# 1-Schematic_SAO_HACKGDL_2025.net
KiCad netlist of a schematic drawn in EasyEDA
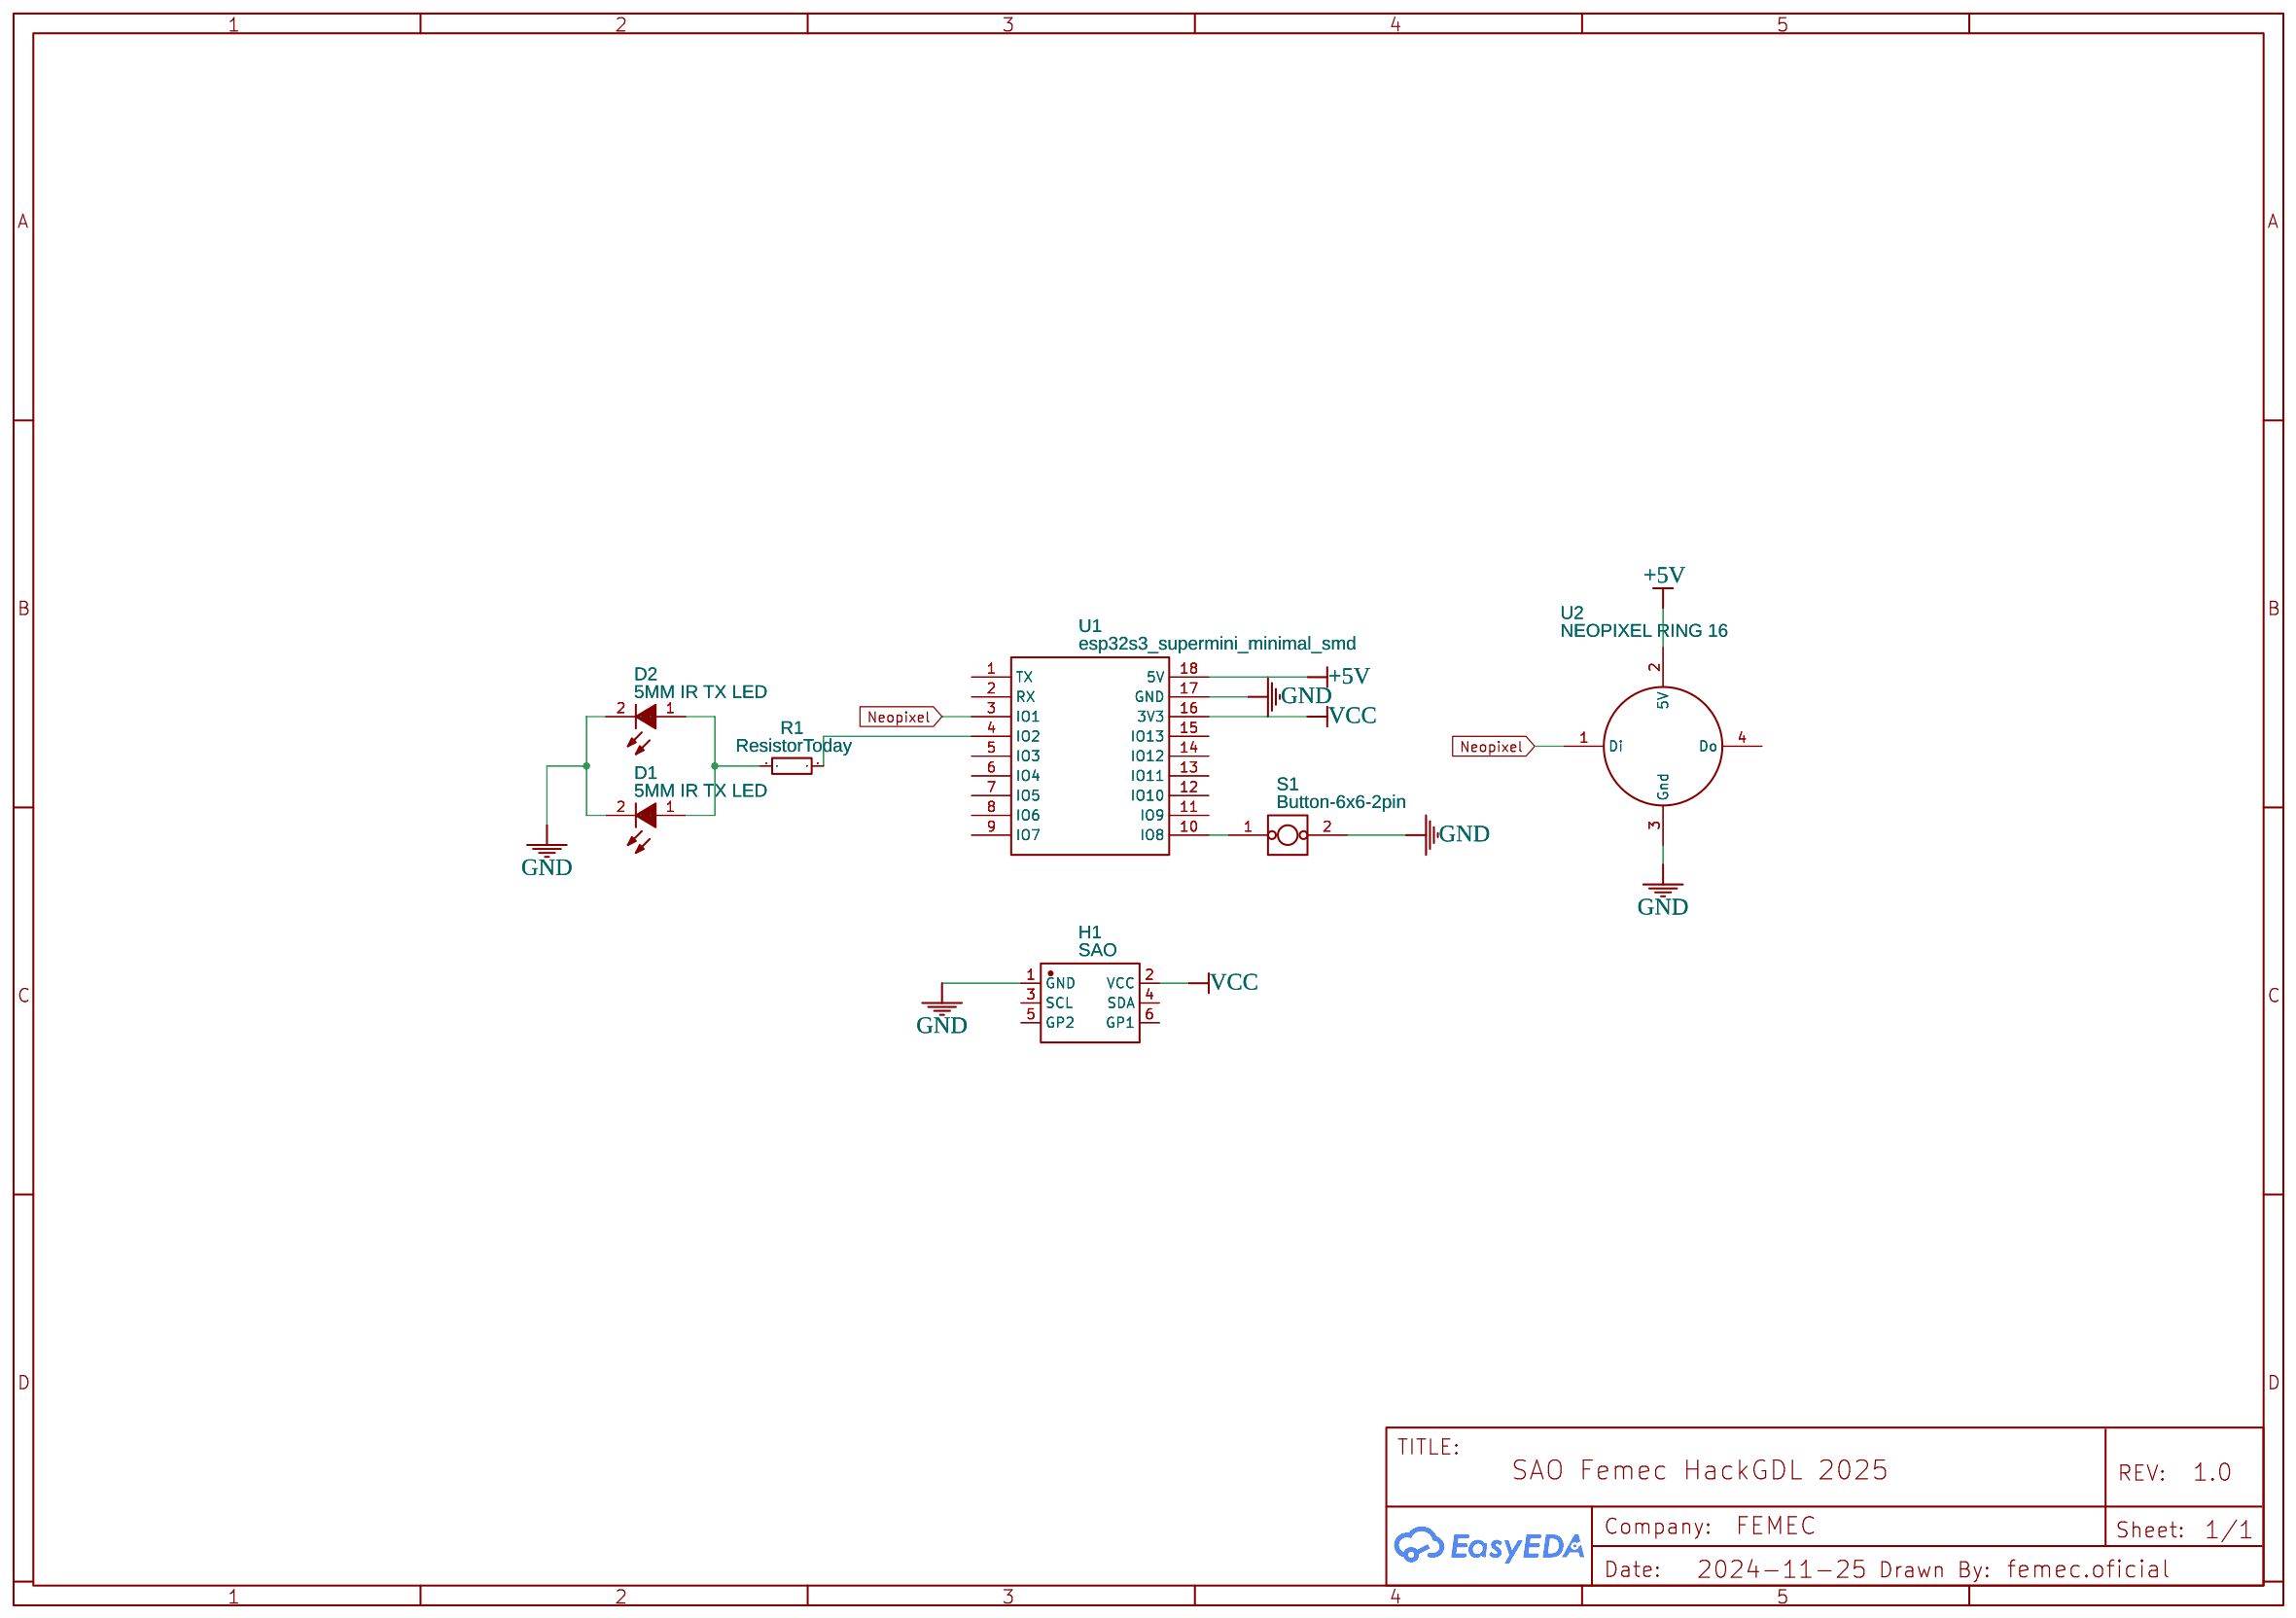
[diagram p0: schematic sheet]

(export (version "E")
  (design (tool "Eeschema 10.0.6"))
  (components
    (comp (ref "D1")
      (value "5MM IR TX LED")
      (fields (field (name "Manufacturer Part") "5600") (field (name "Manufacturer") "VccLite"))
      (libsource (lib "") (part "3mm Green TH LED 5600"))
    )
    (comp (ref "D2")
      (value "5MM IR TX LED")
      (fields (field (name "Manufacturer Part") "5600") (field (name "Manufacturer") "VccLite"))
      (libsource (lib "") (part "3mm Green TH LED 5600"))
    )
    (comp (ref "H1") (value "SAO") (libsource (lib "") (part "SAO")))
    (comp (ref "R1")
      (value "ResistorToday")
      (fields (field (name "Manufacturer Part") "EWWR0001J20R0T9"))
      (libsource (lib "") (part "RESISTOR NORMAL"))
    )
    (comp (ref "S1") (value "Button-6x6-2pin") (libsource (lib "") (part "Button-6x6-2pin")))
    (comp (ref "U1")
      (value "esp32s3_supermini_minimal_smd")
      (libsource (lib "") (part "esp32s3_supermini_minimal_smd"))
    )
    (comp (ref "U2") (value "NEOPIXEL RING 16") (libsource (lib "") (part "NEOPIXEL RING 16")))
  )
  (nets
    (net (code "1") (name "+5V") (class "Default")
      (node (ref "U1") (pin "18") (pinfunction "5V_18") (pintype "unspecified"))
      (node (ref "U2") (pin "2") (pinfunction "5V_2") (pintype "unspecified"))
    )
    (net (code "2") (name "GND") (class "Default")
      (node (ref "D1") (pin "2") (pinfunction "K_2") (pintype "unspecified"))
      (node (ref "D2") (pin "2") (pinfunction "K_2") (pintype "unspecified"))
      (node (ref "H1") (pin "1") (pinfunction "GND_1") (pintype "unspecified"))
      (node (ref "S1") (pin "2") (pintype "unspecified"))
      (node (ref "U1") (pin "17") (pinfunction "GND_17") (pintype "unspecified"))
      (node (ref "U2") (pin "3") (pinfunction "Gnd_3") (pintype "unspecified"))
    )
    (net (code "3") (name "Neopixel") (class "Default")
      (node (ref "U1") (pin "3") (pinfunction "IO1_3") (pintype "unspecified"))
      (node (ref "U2") (pin "1") (pinfunction "Di_1") (pintype "unspecified"))
    )
    (net (code "4") (name "Net-(D1-A)") (class "Default")
      (node (ref "D1") (pin "1") (pinfunction "A_1") (pintype "unspecified"))
      (node (ref "D2") (pin "1") (pinfunction "A_1") (pintype "unspecified"))
      (node (ref "R1") (pin "1") (pinfunction "1_1") (pintype "unspecified"))
    )
    (net (code "5") (name "Net-(U1-IO2)") (class "Default")
      (node (ref "R1") (pin "2") (pinfunction "2_2") (pintype "unspecified"))
      (node (ref "U1") (pin "4") (pinfunction "IO2_4") (pintype "unspecified"))
    )
    (net (code "6") (name "Net-(U1-IO8)") (class "Default")
      (node (ref "S1") (pin "1") (pintype "unspecified"))
      (node (ref "U1") (pin "10") (pinfunction "IO8_10") (pintype "unspecified"))
    )
    (net (code "7") (name "VCC") (class "Default")
      (node (ref "H1") (pin "2") (pinfunction "VCC_2") (pintype "unspecified"))
      (node (ref "U1") (pin "16") (pinfunction "3V3_16") (pintype "unspecified"))
    )
    (net (code "8") (name "unconnected-(H1-GP1-Pad6)") (class "Default")
      (node (ref "H1") (pin "6") (pinfunction "GP1_6") (pintype "unspecified"))
    )
    (net (code "9") (name "unconnected-(H1-GP2-Pad5)") (class "Default")
      (node (ref "H1") (pin "5") (pinfunction "GP2_5") (pintype "unspecified"))
    )
    (net (code "10") (name "unconnected-(H1-SCL-Pad3)") (class "Default")
      (node (ref "H1") (pin "3") (pinfunction "SCL_3") (pintype "unspecified"))
    )
    (net (code "11") (name "unconnected-(H1-SDA-Pad4)") (class "Default")
      (node (ref "H1") (pin "4") (pinfunction "SDA_4") (pintype "unspecified"))
    )
    (net (code "12") (name "unconnected-(U1-IO3-Pad5)") (class "Default")
      (node (ref "U1") (pin "5") (pinfunction "IO3_5") (pintype "unspecified"))
    )
    (net (code "13") (name "unconnected-(U1-IO4-Pad6)") (class "Default")
      (node (ref "U1") (pin "6") (pinfunction "IO4_6") (pintype "unspecified"))
    )
    (net (code "14") (name "unconnected-(U1-IO5-Pad7)") (class "Default")
      (node (ref "U1") (pin "7") (pinfunction "IO5_7") (pintype "unspecified"))
    )
    (net (code "15") (name "unconnected-(U1-IO6-Pad8)") (class "Default")
      (node (ref "U1") (pin "8") (pinfunction "IO6_8") (pintype "unspecified"))
    )
    (net (code "16") (name "unconnected-(U1-IO7-Pad9)") (class "Default")
      (node (ref "U1") (pin "9") (pinfunction "IO7_9") (pintype "unspecified"))
    )
    (net (code "17") (name "unconnected-(U1-IO9-Pad11)") (class "Default")
      (node (ref "U1") (pin "11") (pinfunction "IO9_11") (pintype "unspecified"))
    )
    (net (code "18") (name "unconnected-(U1-IO10-Pad12)") (class "Default")
      (node (ref "U1") (pin "12") (pinfunction "IO10_12") (pintype "unspecified"))
    )
    (net (code "19") (name "unconnected-(U1-IO11-Pad13)") (class "Default")
      (node (ref "U1") (pin "13") (pinfunction "IO11_13") (pintype "unspecified"))
    )
    (net (code "20") (name "unconnected-(U1-IO12-Pad14)") (class "Default")
      (node (ref "U1") (pin "14") (pinfunction "IO12_14") (pintype "unspecified"))
    )
    (net (code "21") (name "unconnected-(U1-IO13-Pad15)") (class "Default")
      (node (ref "U1") (pin "15") (pinfunction "IO13_15") (pintype "unspecified"))
    )
    (net (code "22") (name "unconnected-(U1-RX-Pad2)") (class "Default")
      (node (ref "U1") (pin "2") (pinfunction "RX_2") (pintype "unspecified"))
    )
    (net (code "23") (name "unconnected-(U1-TX-Pad1)") (class "Default")
      (node (ref "U1") (pin "1") (pinfunction "TX_1") (pintype "unspecified"))
    )
    (net (code "24") (name "unconnected-(U2-Do-Pad4)") (class "Default")
      (node (ref "U2") (pin "4") (pinfunction "Do_4") (pintype "unspecified"))
    )
  )
)
